# Voltage_Source.net
KiCad netlist of a schematic drawn in Altium Designer
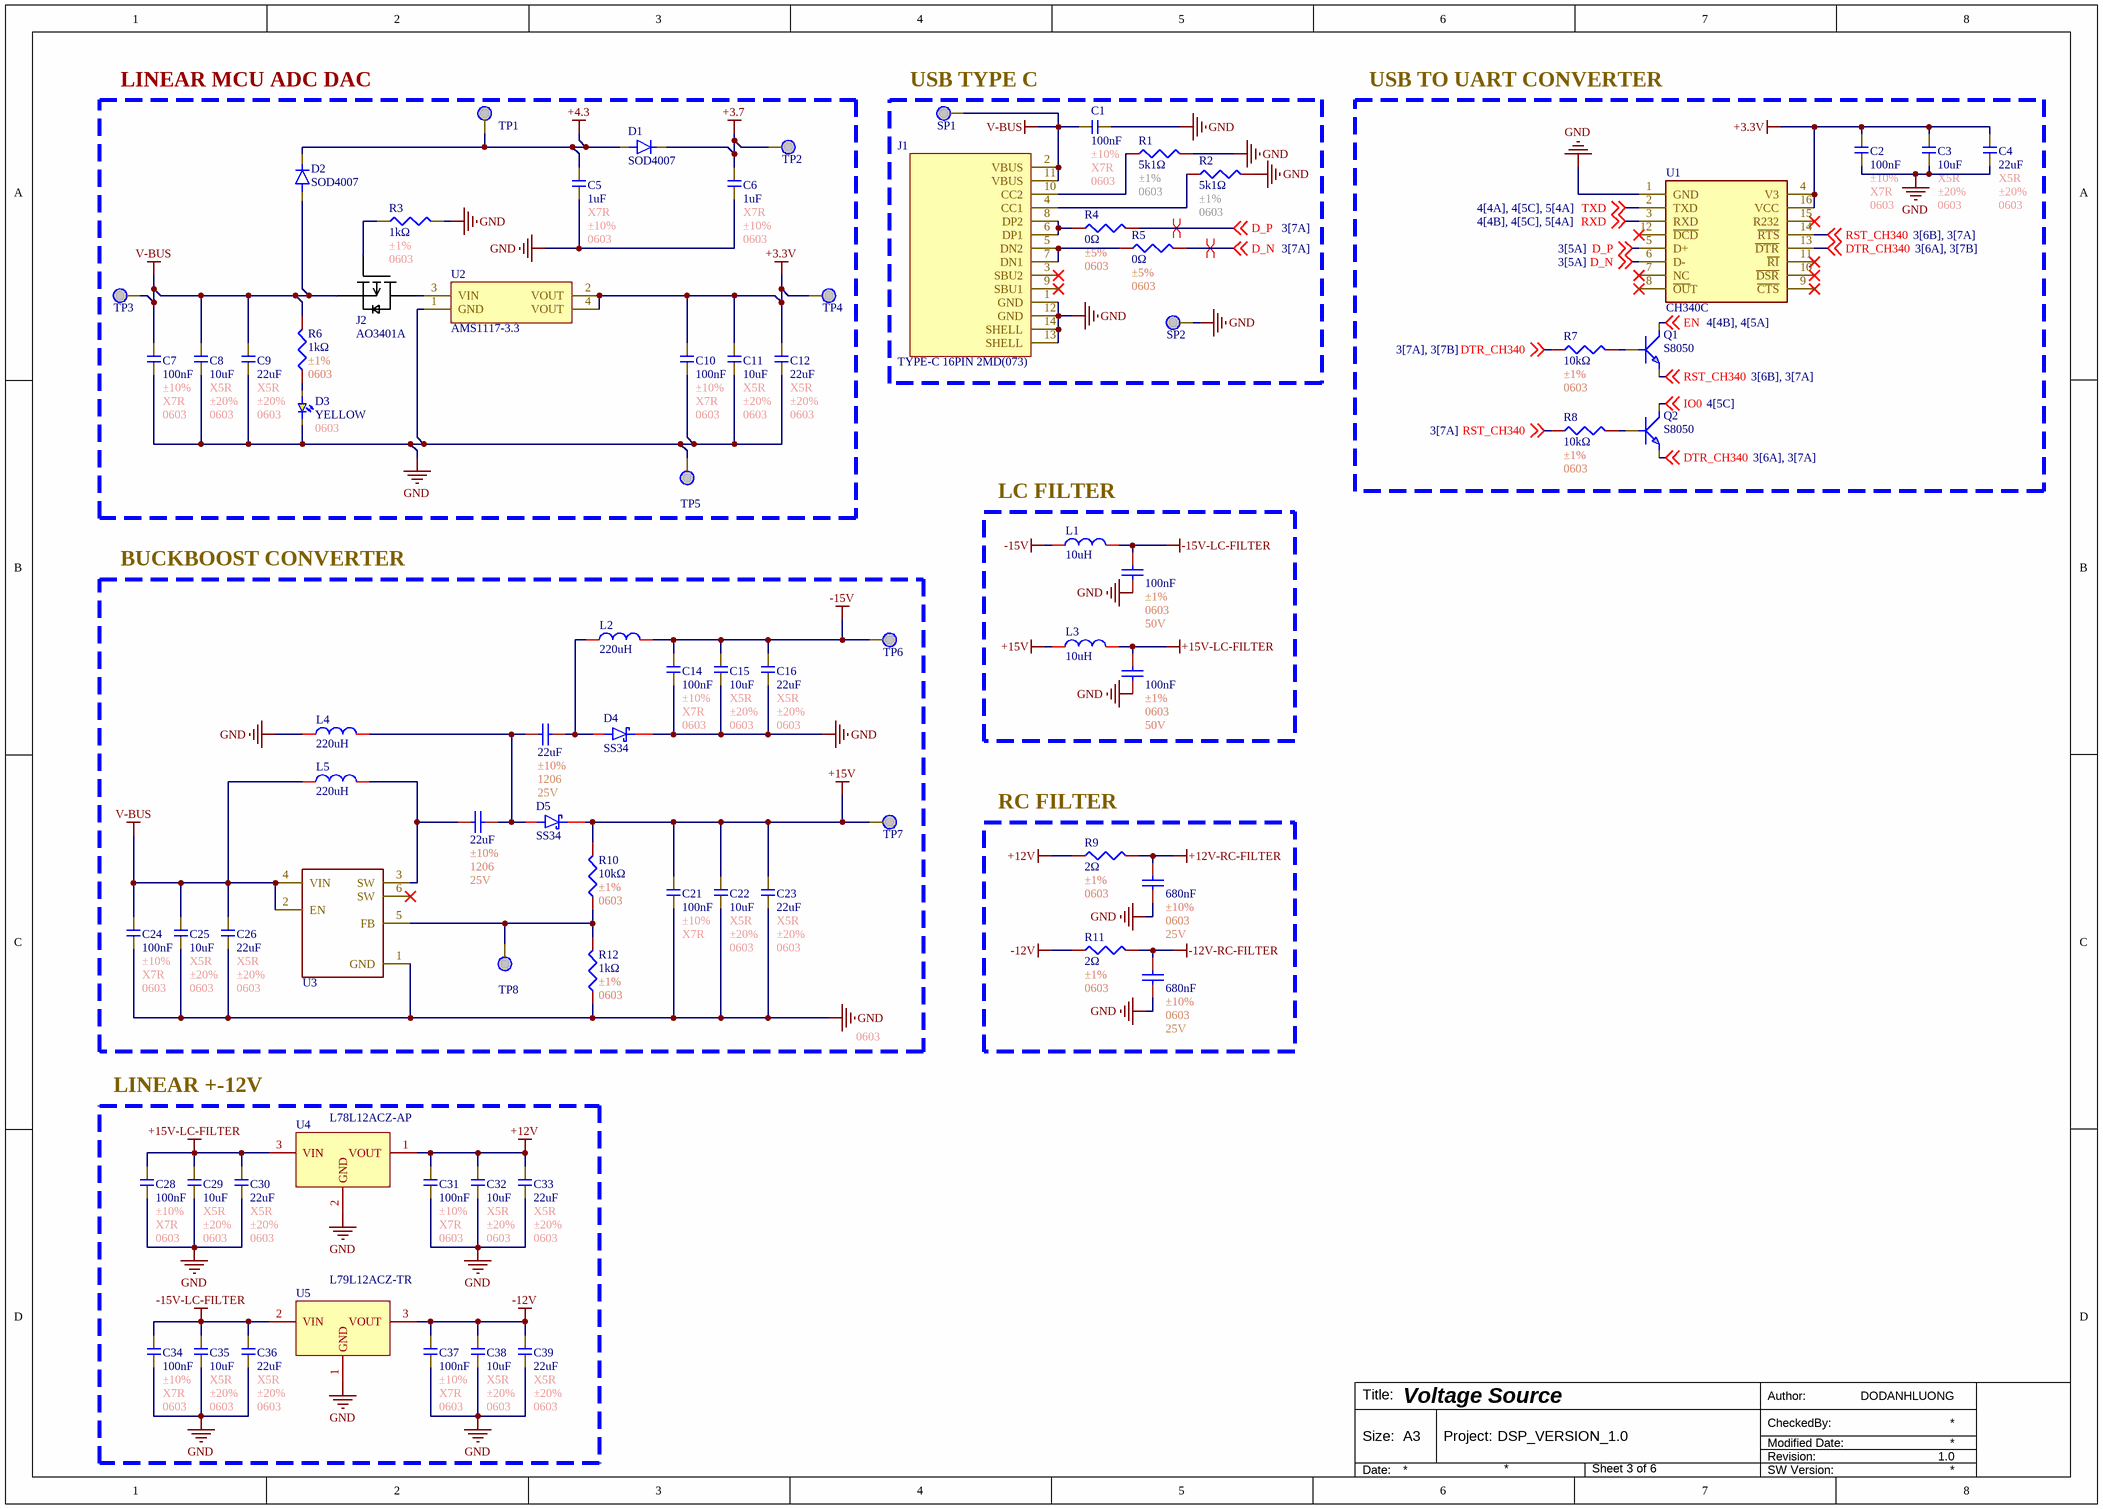
[diagram p0: Voltage Source.SchDoc]

(export (version "E")
  (design (tool "Eeschema 10.0.6"))
  (components
    (comp (ref "C1")
      (value "100nF")
      (footprint "C0603")
      (description "50V 100nF X7R ±10% 0603 Multilayer Ceramic Capacitors MLCC - SMD/SMT ROHS")
      (fields
        (field (name "MANUFACTURER") "YAGEO")
        (field (name "MFR. PART #") "CC0603KRX7R9BB104")
        (field (name "TOLERANCE") "±10%")
        (field (name "TEMPERATURE COEFFICIENT") "X7R")
        (field (name "PACKAGE") "0603")
      )
      (libsource (lib "DSP_VERSION_1.0") (part "C0603_100nF_±10%_X7R"))
    )
    (comp (ref "C2")
      (value "100nF")
      (footprint "C0603")
      (description "50V 100nF X7R ±10% 0603 Multilayer Ceramic Capacitors MLCC - SMD/SMT ROHS")
      (fields
        (field (name "MANUFACTURER") "YAGEO")
        (field (name "MFR. PART #") "CC0603KRX7R9BB104")
        (field (name "TOLERANCE") "±10%")
        (field (name "TEMPERATURE COEFFICIENT") "X7R")
        (field (name "PACKAGE") "0603")
      )
      (libsource (lib "DSP_VERSION_1.0") (part "C0603_100nF_±10%_X7R"))
    )
    (comp (ref "C3")
      (value "10uF")
      (footprint "C0603")
      (description "25V 10uF X5R ±20% 0603 Multilayer Ceramic Capacitors MLCC - SMD/SMT ROHS")
      (fields
        (field (name "MANUFACTURER") "YAGEO")
        (field (name "MFR. PART #") "CC0603MRX5R8BB106")
        (field (name "TEMPERATURE COEFFICIENT") "X5R")
        (field (name "TOLERANCE") "±20%")
        (field (name "PACKAGE") "0603")
      )
      (libsource (lib "DSP_VERSION_1.0") (part "C0603_10uF_±10%_X7R"))
    )
    (comp (ref "C4")
      (value "22uF")
      (footprint "C0603")
      (description "6.3V 22uF X5R ±20% 0603 Multilayer Ceramic Capacitors MLCC - SMD/SMT ROHS")
      (fields
        (field (name "MANUFACTURER") "YAGEO")
        (field (name "MFR. PART #") "CC0603MRX5R5BB226")
        (field (name "TEMPERATURE COEFFICIENT") "X5R")
        (field (name "TOLERANCE") "±20%")
        (field (name "PACKAGE") "0603")
      )
      (libsource (lib "DSP_VERSION_1.0") (part "C0603_22uF_±20%_X5R"))
    )
    (comp (ref "C5")
      (value "1uF")
      (footprint "C0603")
      (description "50V 1uF X7R ±10% 0603 Multilayer Ceramic Capacitors MLCC - SMD/SMT ROHS")
      (fields
        (field (name "MANUFACTURER") "YAGEO")
        (field (name "MFR. PART #") "CC0603KRX7R9BB105")
        (field (name "TEMPERATURE COEFFICIENT") "X7R")
        (field (name "TOLERANCE") "±10%")
        (field (name "PACKAGE") "0603")
      )
      (libsource (lib "DSP_VERSION_1.0") (part "C0603_1uF_±10%_X7R"))
    )
    (comp (ref "C6")
      (value "1uF")
      (footprint "C0603")
      (description "50V 1uF X7R ±10% 0603 Multilayer Ceramic Capacitors MLCC - SMD/SMT ROHS")
      (fields
        (field (name "MANUFACTURER") "YAGEO")
        (field (name "MFR. PART #") "CC0603KRX7R9BB105")
        (field (name "TEMPERATURE COEFFICIENT") "X7R")
        (field (name "TOLERANCE") "±10%")
        (field (name "PACKAGE") "0603")
      )
      (libsource (lib "DSP_VERSION_1.0") (part "C0603_1uF_±10%_X7R"))
    )
    (comp (ref "C7")
      (value "100nF")
      (footprint "C0603")
      (description "50V 100nF X7R ±10% 0603 Multilayer Ceramic Capacitors MLCC - SMD/SMT ROHS")
      (fields
        (field (name "MANUFACTURER") "YAGEO")
        (field (name "MFR. PART #") "CC0603KRX7R9BB104")
        (field (name "TOLERANCE") "±10%")
        (field (name "TEMPERATURE COEFFICIENT") "X7R")
        (field (name "PACKAGE") "0603")
      )
      (libsource (lib "DSP_VERSION_1.0") (part "C0603_100nF_±10%_X7R"))
    )
    (comp (ref "C8")
      (value "10uF")
      (footprint "C0603")
      (description "25V 10uF X5R ±20% 0603 Multilayer Ceramic Capacitors MLCC - SMD/SMT ROHS")
      (fields
        (field (name "MANUFACTURER") "YAGEO")
        (field (name "MFR. PART #") "CC0603MRX5R8BB106")
        (field (name "TEMPERATURE COEFFICIENT") "X5R")
        (field (name "TOLERANCE") "±20%")
        (field (name "PACKAGE") "0603")
      )
      (libsource (lib "DSP_VERSION_1.0") (part "C0603_10uF_±10%_X7R"))
    )
    (comp (ref "C9")
      (value "22uF")
      (footprint "C0603")
      (description "6.3V 22uF X5R ±20% 0603 Multilayer Ceramic Capacitors MLCC - SMD/SMT ROHS")
      (fields
        (field (name "MANUFACTURER") "YAGEO")
        (field (name "MFR. PART #") "CC0603MRX5R5BB226")
        (field (name "TEMPERATURE COEFFICIENT") "X5R")
        (field (name "TOLERANCE") "±20%")
        (field (name "PACKAGE") "0603")
      )
      (libsource (lib "DSP_VERSION_1.0") (part "C0603_22uF_±20%_X5R"))
    )
    (comp (ref "C10")
      (value "100nF")
      (footprint "C0603")
      (description "50V 100nF X7R ±10% 0603 Multilayer Ceramic Capacitors MLCC - SMD/SMT ROHS")
      (fields
        (field (name "MANUFACTURER") "YAGEO")
        (field (name "MFR. PART #") "CC0603KRX7R9BB104")
        (field (name "TOLERANCE") "±10%")
        (field (name "TEMPERATURE COEFFICIENT") "X7R")
        (field (name "PACKAGE") "0603")
      )
      (libsource (lib "DSP_VERSION_1.0") (part "C0603_100nF_±10%_X7R"))
    )
    (comp (ref "C11")
      (value "10uF")
      (footprint "C0603")
      (description "25V 10uF X5R ±20% 0603 Multilayer Ceramic Capacitors MLCC - SMD/SMT ROHS")
      (fields
        (field (name "MANUFACTURER") "YAGEO")
        (field (name "MFR. PART #") "CC0603MRX5R8BB106")
        (field (name "TEMPERATURE COEFFICIENT") "X5R")
        (field (name "TOLERANCE") "±20%")
        (field (name "PACKAGE") "0603")
      )
      (libsource (lib "DSP_VERSION_1.0") (part "C0603_10uF_±10%_X7R"))
    )
    (comp (ref "C12")
      (value "22uF")
      (footprint "C0603")
      (description "6.3V 22uF X5R ±20% 0603 Multilayer Ceramic Capacitors MLCC - SMD/SMT ROHS")
      (fields
        (field (name "MANUFACTURER") "YAGEO")
        (field (name "MFR. PART #") "CC0603MRX5R5BB226")
        (field (name "TEMPERATURE COEFFICIENT") "X5R")
        (field (name "TOLERANCE") "±20%")
        (field (name "PACKAGE") "0603")
      )
      (libsource (lib "DSP_VERSION_1.0") (part "C0603_22uF_±20%_X5R"))
    )
    (comp (ref "C13")
      (value "100nF")
      (footprint "C0603")
      (description "50V 10pF NP0 ±1% 0402 Multilayer Ceramic Capacitors MLCC - SMD/SMT ROHS")
      (fields
        (field (name "MANUFACTURER") "YAGEO")
        (field (name "MFR. PART #") "CC0402FRNPO9BN100")
        (field (name "TOLERANCE") "±1%")
        (field (name "PACKAGE") "0603")
        (field (name "VOLTAGE RATING") "50V")
      )
      (libsource (lib "Capital") (part "C0603_100nF_±1%"))
    )
    (comp (ref "C14")
      (value "100nF")
      (footprint "C0603")
      (description "50V 100nF X7R ±10% 0603 Multilayer Ceramic Capacitors MLCC - SMD/SMT ROHS")
      (fields
        (field (name "MANUFACTURER") "YAGEO")
        (field (name "MFR. PART #") "CC0603KRX7R9BB104")
        (field (name "TOLERANCE") "±10%")
        (field (name "TEMPERATURE COEFFICIENT") "X7R")
        (field (name "PACKAGE") "0603")
      )
      (libsource (lib "DSP_VERSION_1.0") (part "C0603_100nF_±10%_X7R"))
    )
    (comp (ref "C15")
      (value "10uF")
      (footprint "C0603")
      (description "25V 10uF X5R ±20% 0603 Multilayer Ceramic Capacitors MLCC - SMD/SMT ROHS")
      (fields
        (field (name "MANUFACTURER") "YAGEO")
        (field (name "MFR. PART #") "CC0603MRX5R8BB106")
        (field (name "TEMPERATURE COEFFICIENT") "X5R")
        (field (name "TOLERANCE") "±20%")
        (field (name "PACKAGE") "0603")
      )
      (libsource (lib "DSP_VERSION_1.0") (part "C0603_10uF_±10%_X7R"))
    )
    (comp (ref "C16")
      (value "22uF")
      (footprint "C0603")
      (description "6.3V 22uF X5R ±20% 0603 Multilayer Ceramic Capacitors MLCC - SMD/SMT ROHS")
      (fields
        (field (name "MANUFACTURER") "YAGEO")
        (field (name "MFR. PART #") "CC0603MRX5R5BB226")
        (field (name "TEMPERATURE COEFFICIENT") "X5R")
        (field (name "TOLERANCE") "±20%")
        (field (name "PACKAGE") "0603")
      )
      (libsource (lib "DSP_VERSION_1.0") (part "C0603_22uF_±20%_X5R"))
    )
    (comp (ref "C17")
      (value "100nF")
      (footprint "C0603")
      (description "50V 10pF NP0 ±1% 0402 Multilayer Ceramic Capacitors MLCC - SMD/SMT ROHS")
      (fields
        (field (name "MANUFACTURER") "YAGEO")
        (field (name "MFR. PART #") "CC0402FRNPO9BN100")
        (field (name "TOLERANCE") "±1%")
        (field (name "PACKAGE") "0603")
        (field (name "VOLTAGE RATING") "50V")
      )
      (libsource (lib "Capital") (part "C0603_100nF_±1%"))
    )
    (comp (ref "C18")
      (value "22uF")
      (footprint "C1206")
      (description "25V 22uF X5R ±10% 1206 Multilayer Ceramic Capacitors MLCC - SMD/SMT ROHS")
      (fields
        (field (name "MANUFACTURER") "YAGEO")
        (field (name "MFR. PART #") "CC1206KKX5R8BB226")
        (field (name "TOLERANCE") "±10%")
        (field (name "PACKAGE") "1206")
        (field (name "VOLTAGE RATING") "25V")
      )
      (libsource (lib "Capital") (part "C1206_22uF_±1%"))
    )
    (comp (ref "C19")
      (value "22uF")
      (footprint "C1206")
      (description "25V 22uF X5R ±10% 1206 Multilayer Ceramic Capacitors MLCC - SMD/SMT ROHS")
      (fields
        (field (name "MANUFACTURER") "YAGEO")
        (field (name "MFR. PART #") "CC1206KKX5R8BB226")
        (field (name "TOLERANCE") "±10%")
        (field (name "PACKAGE") "1206")
        (field (name "VOLTAGE RATING") "25V")
      )
      (libsource (lib "Capital") (part "C1206_22uF_±1%"))
    )
    (comp (ref "C20")
      (value "680nF")
      (footprint "C0603")
      (description "25V 680nF X5R ±10% 0603 Multilayer Ceramic Capacitors MLCC - SMD/SMT ROHS")
      (fields
        (field (name "MANUFACTURER") "YAGEO")
        (field (name "MFR. PART #") "CC0603KRX5R8BB684")
        (field (name "TOLERANCE") "±10%")
        (field (name "PACKAGE") "0603")
        (field (name "VOLTAGE RATING") "25V")
      )
      (libsource (lib "Capital") (part "C0603_680nF_±1%"))
    )
    (comp (ref "C21")
      (value "100nF")
      (footprint "C0603")
      (description "50V 100nF X7R ±10% 0603 Multilayer Ceramic Capacitors MLCC - SMD/SMT ROHS")
      (fields
        (field (name "MANUFACTURER") "YAGEO")
        (field (name "MFR. PART #") "CC0603KRX7R9BB104")
        (field (name "TOLERANCE") "±10%")
        (field (name "TEMPERATURE COEFFICIENT") "X7R")
        (field (name "PACKAGE") "0603")
      )
      (libsource (lib "DSP_VERSION_1.0") (part "C0603_100nF_±10%_X7R"))
    )
    (comp (ref "C22")
      (value "10uF")
      (footprint "C0603")
      (description "25V 10uF X5R ±20% 0603 Multilayer Ceramic Capacitors MLCC - SMD/SMT ROHS")
      (fields
        (field (name "MANUFACTURER") "YAGEO")
        (field (name "MFR. PART #") "CC0603MRX5R8BB106")
        (field (name "TEMPERATURE COEFFICIENT") "X5R")
        (field (name "TOLERANCE") "±20%")
        (field (name "PACKAGE") "0603")
      )
      (libsource (lib "DSP_VERSION_1.0") (part "C0603_10uF_±10%_X7R"))
    )
    (comp (ref "C23")
      (value "22uF")
      (footprint "C0603")
      (description "6.3V 22uF X5R ±20% 0603 Multilayer Ceramic Capacitors MLCC - SMD/SMT ROHS")
      (fields
        (field (name "MANUFACTURER") "YAGEO")
        (field (name "MFR. PART #") "CC0603MRX5R5BB226")
        (field (name "TEMPERATURE COEFFICIENT") "X5R")
        (field (name "TOLERANCE") "±20%")
        (field (name "PACKAGE") "0603")
      )
      (libsource (lib "DSP_VERSION_1.0") (part "C0603_22uF_±20%_X5R"))
    )
    (comp (ref "C24")
      (value "100nF")
      (footprint "C0603")
      (description "50V 100nF X7R ±10% 0603 Multilayer Ceramic Capacitors MLCC - SMD/SMT ROHS")
      (fields
        (field (name "MANUFACTURER") "YAGEO")
        (field (name "MFR. PART #") "CC0603KRX7R9BB104")
        (field (name "TOLERANCE") "±10%")
        (field (name "TEMPERATURE COEFFICIENT") "X7R")
        (field (name "PACKAGE") "0603")
      )
      (libsource (lib "DSP_VERSION_1.0") (part "C0603_100nF_±10%_X7R"))
    )
    (comp (ref "C25")
      (value "10uF")
      (footprint "C0603")
      (description "25V 10uF X5R ±20% 0603 Multilayer Ceramic Capacitors MLCC - SMD/SMT ROHS")
      (fields
        (field (name "MANUFACTURER") "YAGEO")
        (field (name "MFR. PART #") "CC0603MRX5R8BB106")
        (field (name "TEMPERATURE COEFFICIENT") "X5R")
        (field (name "TOLERANCE") "±20%")
        (field (name "PACKAGE") "0603")
      )
      (libsource (lib "DSP_VERSION_1.0") (part "C0603_10uF_±10%_X7R"))
    )
    (comp (ref "C26")
      (value "22uF")
      (footprint "C0603")
      (description "6.3V 22uF X5R ±20% 0603 Multilayer Ceramic Capacitors MLCC - SMD/SMT ROHS")
      (fields
        (field (name "MANUFACTURER") "YAGEO")
        (field (name "MFR. PART #") "CC0603MRX5R5BB226")
        (field (name "TEMPERATURE COEFFICIENT") "X5R")
        (field (name "TOLERANCE") "±20%")
        (field (name "PACKAGE") "0603")
      )
      (libsource (lib "DSP_VERSION_1.0") (part "C0603_22uF_±20%_X5R"))
    )
    (comp (ref "C27")
      (value "680nF")
      (footprint "C0603")
      (description "25V 680nF X5R ±10% 0603 Multilayer Ceramic Capacitors MLCC - SMD/SMT ROHS")
      (fields
        (field (name "MANUFACTURER") "YAGEO")
        (field (name "MFR. PART #") "CC0603KRX5R8BB684")
        (field (name "TOLERANCE") "±10%")
        (field (name "PACKAGE") "0603")
        (field (name "VOLTAGE RATING") "25V")
      )
      (libsource (lib "Capital") (part "C0603_680nF_±1%"))
    )
    (comp (ref "C28")
      (value "100nF")
      (footprint "C0603")
      (description "50V 100nF X7R ±10% 0603 Multilayer Ceramic Capacitors MLCC - SMD/SMT ROHS")
      (fields
        (field (name "MANUFACTURER") "YAGEO")
        (field (name "MFR. PART #") "CC0603KRX7R9BB104")
        (field (name "TOLERANCE") "±10%")
        (field (name "TEMPERATURE COEFFICIENT") "X7R")
        (field (name "PACKAGE") "0603")
      )
      (libsource (lib "DSP_VERSION_1.0") (part "C0603_100nF_±10%_X7R"))
    )
    (comp (ref "C29")
      (value "10uF")
      (footprint "C0603")
      (description "25V 10uF X5R ±20% 0603 Multilayer Ceramic Capacitors MLCC - SMD/SMT ROHS")
      (fields
        (field (name "MANUFACTURER") "YAGEO")
        (field (name "MFR. PART #") "CC0603MRX5R8BB106")
        (field (name "TEMPERATURE COEFFICIENT") "X5R")
        (field (name "TOLERANCE") "±20%")
        (field (name "PACKAGE") "0603")
      )
      (libsource (lib "DSP_VERSION_1.0") (part "C0603_10uF_±10%_X7R"))
    )
    (comp (ref "C30")
      (value "22uF")
      (footprint "C0603")
      (description "6.3V 22uF X5R ±20% 0603 Multilayer Ceramic Capacitors MLCC - SMD/SMT ROHS")
      (fields
        (field (name "MANUFACTURER") "YAGEO")
        (field (name "MFR. PART #") "CC0603MRX5R5BB226")
        (field (name "TEMPERATURE COEFFICIENT") "X5R")
        (field (name "TOLERANCE") "±20%")
        (field (name "PACKAGE") "0603")
      )
      (libsource (lib "DSP_VERSION_1.0") (part "C0603_22uF_±20%_X5R"))
    )
    (comp (ref "C31")
      (value "100nF")
      (footprint "C0603")
      (description "50V 100nF X7R ±10% 0603 Multilayer Ceramic Capacitors MLCC - SMD/SMT ROHS")
      (fields
        (field (name "MANUFACTURER") "YAGEO")
        (field (name "MFR. PART #") "CC0603KRX7R9BB104")
        (field (name "TOLERANCE") "±10%")
        (field (name "TEMPERATURE COEFFICIENT") "X7R")
        (field (name "PACKAGE") "0603")
      )
      (libsource (lib "DSP_VERSION_1.0") (part "C0603_100nF_±10%_X7R"))
    )
    (comp (ref "C32")
      (value "10uF")
      (footprint "C0603")
      (description "25V 10uF X5R ±20% 0603 Multilayer Ceramic Capacitors MLCC - SMD/SMT ROHS")
      (fields
        (field (name "MANUFACTURER") "YAGEO")
        (field (name "MFR. PART #") "CC0603MRX5R8BB106")
        (field (name "TEMPERATURE COEFFICIENT") "X5R")
        (field (name "TOLERANCE") "±20%")
        (field (name "PACKAGE") "0603")
      )
      (libsource (lib "DSP_VERSION_1.0") (part "C0603_10uF_±10%_X7R"))
    )
    (comp (ref "C33")
      (value "22uF")
      (footprint "C0603")
      (description "6.3V 22uF X5R ±20% 0603 Multilayer Ceramic Capacitors MLCC - SMD/SMT ROHS")
      (fields
        (field (name "MANUFACTURER") "YAGEO")
        (field (name "MFR. PART #") "CC0603MRX5R5BB226")
        (field (name "TEMPERATURE COEFFICIENT") "X5R")
        (field (name "TOLERANCE") "±20%")
        (field (name "PACKAGE") "0603")
      )
      (libsource (lib "DSP_VERSION_1.0") (part "C0603_22uF_±20%_X5R"))
    )
    (comp (ref "C34")
      (value "100nF")
      (footprint "C0603")
      (description "50V 100nF X7R ±10% 0603 Multilayer Ceramic Capacitors MLCC - SMD/SMT ROHS")
      (fields
        (field (name "MANUFACTURER") "YAGEO")
        (field (name "MFR. PART #") "CC0603KRX7R9BB104")
        (field (name "TOLERANCE") "±10%")
        (field (name "TEMPERATURE COEFFICIENT") "X7R")
        (field (name "PACKAGE") "0603")
      )
      (libsource (lib "DSP_VERSION_1.0") (part "C0603_100nF_±10%_X7R"))
    )
    (comp (ref "C35")
      (value "10uF")
      (footprint "C0603")
      (description "25V 10uF X5R ±20% 0603 Multilayer Ceramic Capacitors MLCC - SMD/SMT ROHS")
      (fields
        (field (name "MANUFACTURER") "YAGEO")
        (field (name "MFR. PART #") "CC0603MRX5R8BB106")
        (field (name "TEMPERATURE COEFFICIENT") "X5R")
        (field (name "TOLERANCE") "±20%")
        (field (name "PACKAGE") "0603")
      )
      (libsource (lib "DSP_VERSION_1.0") (part "C0603_10uF_±10%_X7R"))
    )
    (comp (ref "C36")
      (value "22uF")
      (footprint "C0603")
      (description "6.3V 22uF X5R ±20% 0603 Multilayer Ceramic Capacitors MLCC - SMD/SMT ROHS")
      (fields
        (field (name "MANUFACTURER") "YAGEO")
        (field (name "MFR. PART #") "CC0603MRX5R5BB226")
        (field (name "TEMPERATURE COEFFICIENT") "X5R")
        (field (name "TOLERANCE") "±20%")
        (field (name "PACKAGE") "0603")
      )
      (libsource (lib "DSP_VERSION_1.0") (part "C0603_22uF_±20%_X5R"))
    )
    (comp (ref "C37")
      (value "100nF")
      (footprint "C0603")
      (description "50V 100nF X7R ±10% 0603 Multilayer Ceramic Capacitors MLCC - SMD/SMT ROHS")
      (fields
        (field (name "MANUFACTURER") "YAGEO")
        (field (name "MFR. PART #") "CC0603KRX7R9BB104")
        (field (name "TOLERANCE") "±10%")
        (field (name "TEMPERATURE COEFFICIENT") "X7R")
        (field (name "PACKAGE") "0603")
      )
      (libsource (lib "DSP_VERSION_1.0") (part "C0603_100nF_±10%_X7R"))
    )
    (comp (ref "C38")
      (value "10uF")
      (footprint "C0603")
      (description "25V 10uF X5R ±20% 0603 Multilayer Ceramic Capacitors MLCC - SMD/SMT ROHS")
      (fields
        (field (name "MANUFACTURER") "YAGEO")
        (field (name "MFR. PART #") "CC0603MRX5R8BB106")
        (field (name "TEMPERATURE COEFFICIENT") "X5R")
        (field (name "TOLERANCE") "±20%")
        (field (name "PACKAGE") "0603")
      )
      (libsource (lib "DSP_VERSION_1.0") (part "C0603_10uF_±10%_X7R"))
    )
    (comp (ref "C39")
      (value "22uF")
      (footprint "C0603")
      (description "6.3V 22uF X5R ±20% 0603 Multilayer Ceramic Capacitors MLCC - SMD/SMT ROHS")
      (fields
        (field (name "MANUFACTURER") "YAGEO")
        (field (name "MFR. PART #") "CC0603MRX5R5BB226")
        (field (name "TEMPERATURE COEFFICIENT") "X5R")
        (field (name "TOLERANCE") "±20%")
        (field (name "PACKAGE") "0603")
      )
      (libsource (lib "DSP_VERSION_1.0") (part "C0603_22uF_±20%_X5R"))
    )
    (comp (ref "D1")
      (value "SOD4007")
      (footprint "SOD4007")
      (description "1A Independent 1kV 1.1V@1A SOD-123FL Diodes - General Purpose ROHS")
      (fields
        (field (name "MANUFACTURER") "MDD(Microdiode Semiconductor)")
        (field (name "LCSC PART #") "C18124")
      )
      (libsource (lib "Diode") (part "SOD4007"))
    )
    (comp (ref "D2")
      (value "SOD4007")
      (footprint "SOD4007")
      (description "1A Independent 1kV 1.1V@1A SOD-123FL Diodes - General Purpose ROHS")
      (fields
        (field (name "MANUFACTURER") "MDD(Microdiode Semiconductor)")
        (field (name "LCSC PART #") "C18124")
      )
      (libsource (lib "Diode") (part "SOD4007"))
    )
    (comp (ref "D3")
      (value "YELLOW")
      (footprint "LED0603")
      (description "25mcd~40mcd Water Clear -40℃~+85℃ 624nm Red 120° 60mW 0402 LED Indication - Discrete ROHS")
      (fields
        (field (name "MANUFACTURER") "XINGLIGHT")
        (field (name "MFR. PART #") "XL-1005UGC")
        (field (name "PACKAGE") "0603")
      )
      (libsource (lib "LED") (part "D0603_YELLOW"))
    )
    (comp (ref "D4")
      (value "SS34")
      (footprint "SS34")
      (description "40V Independent 3A 550mV@3A SMA(DO-214AC) Schottky Diodes ROHS")
      (fields
        (field (name "MANUFACTURER") "MDD(Microdiode Semiconductor)")
        (field (name "LCSC PART #") "C8678")
      )
      (libsource (lib "Diode") (part "SS34"))
    )
    (comp (ref "D5")
      (value "SS34")
      (footprint "SS34")
      (description "40V Independent 3A 550mV@3A SMA(DO-214AC) Schottky Diodes ROHS")
      (fields
        (field (name "MANUFACTURER") "MDD(Microdiode Semiconductor)")
        (field (name "LCSC PART #") "C8678")
      )
      (libsource (lib "Diode") (part "SS34"))
    )
    (comp (ref "J1")
      (value "TYPE-C 16PIN 2MD(073)")
      (footprint "TYPE_C_FAMALE")
      (description "3A 1 Surface Mount, Right Angle 16P Female -25℃~+85℃ Type-C SMD USB Connectors ROHS")
      (fields (field (name "MANUFACTURER") "SHOU HAN") (field (name "LCSC PART #") "C2765186"))
      (libsource (lib "Connector") (part "TYPE_C_FAMALE_16PIN"))
    )
    (comp (ref "J2")
      (value "AO3401A")
      (footprint "AO3401A")
      (description "30V 4A 900mV@250uA 1 P-Channel SOT-23 MOSFETs ROHS")
      (fields (field (name "MANUFACTURER") "AOS") (field (name "LCSC PART #") "C15127"))
      (libsource (lib "DSP_VERSION_1.0") (part "AO3401"))
    )
    (comp (ref "L1")
      (value "10uH")
      (footprint "CD43")
      (description "1.15A 10uH Unshielded Inductor ±20% SMD,4x4.5mm Power Inductors ROHS")
      (fields (field (name "MANUFACTURER") "ZE") (field (name "MFR. PART #") "CD43-100M"))
      (libsource (lib "Inductor") (part "CD4-10UH"))
    )
    (comp (ref "L2")
      (value "220uH")
      (footprint "CD43")
      (description "360mA 220uH ±20% SMD,4.5x4x3.2mm Power Inductors ROHS")
      (fields (field (name "MANUFACTURER") "YJYCOIN") (field (name "MFR. PART #") "CD43YP0403-221M"))
      (libsource (lib "Inductor") (part "CD4-220UH"))
    )
    (comp (ref "L3")
      (value "10uH")
      (footprint "CD43")
      (description "1.15A 10uH Unshielded Inductor ±20% SMD,4x4.5mm Power Inductors ROHS")
      (fields (field (name "MANUFACTURER") "ZE") (field (name "MFR. PART #") "CD43-100M"))
      (libsource (lib "Inductor") (part "CD4-10UH"))
    )
    (comp (ref "L4")
      (value "220uH")
      (footprint "CD43")
      (description "360mA 220uH ±20% SMD,4.5x4x3.2mm Power Inductors ROHS")
      (fields (field (name "MANUFACTURER") "YJYCOIN") (field (name "MFR. PART #") "CD43YP0403-221M"))
      (libsource (lib "Inductor") (part "CD4-220UH"))
    )
    (comp (ref "L5")
      (value "220uH")
      (footprint "CD43")
      (description "360mA 220uH ±20% SMD,4.5x4x3.2mm Power Inductors ROHS")
      (fields (field (name "MANUFACTURER") "YJYCOIN") (field (name "MFR. PART #") "CD43YP0403-221M"))
      (libsource (lib "Inductor") (part "CD4-220UH"))
    )
    (comp (ref "Q1")
      (value "S8050")
      (footprint "S8050")
      (description "25V 300mW 500mA SOT-23 Bipolar (BJT) ROHS")
      (fields (field (name "MANUFACTURER") "JSMSEMI") (field (name "LCSC PART #") "C916390"))
      (libsource (lib "Transistor") (part "S8050"))
    )
    (comp (ref "Q2")
      (value "S8050")
      (footprint "S8050")
      (description "25V 300mW 500mA SOT-23 Bipolar (BJT) ROHS")
      (fields (field (name "MANUFACTURER") "JSMSEMI") (field (name "LCSC PART #") "C916390"))
      (libsource (lib "Transistor") (part "S8050"))
    )
    (comp (ref "R1")
      (value "5k1Ω")
      (footprint "R0603")
      (description "100mW Thick Film Resistor 75V ±100ppm/℃ ±1% 5.1kΩ 0603 Chip Resistor - Surface Mount ROHS")
      (fields
        (field (name "MANUFACTURER") "FOJAN")
        (field (name "MFR. PART #") "FRC0603F5101TS")
        (field (name "TOLERANCE") "±1%")
        (field (name "PACKAGE") "0603")
      )
      (libsource (lib "Resistor") (part "R0603_5k1Ω_±1%"))
    )
    (comp (ref "R2")
      (value "5k1Ω")
      (footprint "R0603")
      (description "100mW Thick Film Resistor 75V ±100ppm/℃ ±1% 5.1kΩ 0603 Chip Resistor - Surface Mount ROHS")
      (fields
        (field (name "MANUFACTURER") "FOJAN")
        (field (name "MFR. PART #") "FRC0603F5101TS")
        (field (name "TOLERANCE") "±1%")
        (field (name "PACKAGE") "0603")
      )
      (libsource (lib "Resistor") (part "R0603_5k1Ω_±1%"))
    )
    (comp (ref "R3")
      (value "1kΩ")
      (footprint "R0603")
      (description "100mW Thick Film Resistor 75V ±100ppm/℃ ±1% 1kΩ 0603 Chip Resistor - Surface Mount ROHS")
      (fields
        (field (name "MANUFACTURER") "YAGEO")
        (field (name "MFR. PART #") "RC0603FR-071KL")
        (field (name "TOLERANCE") "±1%")
        (field (name "PACKAGE") "0603")
      )
      (libsource (lib "DSP_VERSION_1.0") (part "R0603_1kΩ_±1%"))
    )
    (comp (ref "R4")
      (value "0Ω")
      (footprint "R0603")
      (description "100mW Thick Film Resistor 75V ±5% 0Ω 0603 Chip Resistor - Surface Mount ROHS")
      (fields
        (field (name "MANUFACTURER") "YAGEO")
        (field (name "MFR. PART #") "RC0603JR-070RL")
        (field (name "TOLERANCE") "±5%")
        (field (name "PACKAGE") "0603")
      )
      (libsource (lib "Resistor") (part "R0603_0Ω_±5%"))
    )
    (comp (ref "R5")
      (value "0Ω")
      (footprint "R0603")
      (description "100mW Thick Film Resistor 75V ±5% 0Ω 0603 Chip Resistor - Surface Mount ROHS")
      (fields
        (field (name "MANUFACTURER") "YAGEO")
        (field (name "MFR. PART #") "RC0603JR-070RL")
        (field (name "TOLERANCE") "±5%")
        (field (name "PACKAGE") "0603")
      )
      (libsource (lib "Resistor") (part "R0603_0Ω_±5%"))
    )
    (comp (ref "R6")
      (value "1kΩ")
      (footprint "R0603")
      (description "62.5mW Thick Film Resistor 50V ±1% ±200ppm/℃ 10Ω 0402 Chip Resistor - Surface Mount ROHS")
      (fields
        (field (name "MANUFACTURER") "YAGEO")
        (field (name "MFR. PART #") "RC0402FR-0710RL")
        (field (name "TOLERANCE") "±1%")
        (field (name "PACKAGE") "0603")
      )
      (libsource (lib "Resistor") (part "R0603_1kΩ_±1%"))
    )
    (comp (ref "R7")
      (value "10kΩ")
      (footprint "R0603")
      (description "62.5mW Thick Film Resistor 50V ±1% ±200ppm/℃ 10Ω 0402 Chip Resistor - Surface Mount ROHS")
      (fields
        (field (name "MANUFACTURER") "YAGEO")
        (field (name "MFR. PART #") "RC0402FR-0710RL")
        (field (name "TOLERANCE") "±1%")
        (field (name "PACKAGE") "0603")
      )
      (libsource (lib "Resistor") (part "R0603_10kΩ_±1%"))
    )
    (comp (ref "R8")
      (value "10kΩ")
      (footprint "R0603")
      (description "62.5mW Thick Film Resistor 50V ±1% ±200ppm/℃ 10Ω 0402 Chip Resistor - Surface Mount ROHS")
      (fields
        (field (name "MANUFACTURER") "YAGEO")
        (field (name "MFR. PART #") "RC0402FR-0710RL")
        (field (name "TOLERANCE") "±1%")
        (field (name "PACKAGE") "0603")
      )
      (libsource (lib "Resistor") (part "R0603_10kΩ_±1%"))
    )
    (comp (ref "R9")
      (value "2Ω")
      (footprint "R0603")
      (description "100mW Thick Film Resistor 75V ±1% ±200ppm/℃ 2Ω 0603 Chip Resistor - Surface Mount ROHS")
      (fields
        (field (name "MANUFACTURER") "YAGEO")
        (field (name "MFR. PART #") "RC0603FR-072RL")
        (field (name "TOLERANCE") "±1%")
        (field (name "PACKAGE") "0603")
      )
      (libsource (lib "Resistor") (part "R0603_2Ω_±5%"))
    )
    (comp (ref "R10")
      (value "10kΩ")
      (footprint "R0603")
      (description "62.5mW Thick Film Resistor 50V ±1% ±200ppm/℃ 10Ω 0402 Chip Resistor - Surface Mount ROHS")
      (fields
        (field (name "MANUFACTURER") "YAGEO")
        (field (name "MFR. PART #") "RC0402FR-0710RL")
        (field (name "TOLERANCE") "±1%")
        (field (name "PACKAGE") "0603")
      )
      (libsource (lib "Resistor") (part "R0603_10kΩ_±1%"))
    )
    (comp (ref "R11")
      (value "2Ω")
      (footprint "R0603")
      (description "100mW Thick Film Resistor 75V ±1% ±200ppm/℃ 2Ω 0603 Chip Resistor - Surface Mount ROHS")
      (fields
        (field (name "MANUFACTURER") "YAGEO")
        (field (name "MFR. PART #") "RC0603FR-072RL")
        (field (name "TOLERANCE") "±1%")
        (field (name "PACKAGE") "0603")
      )
      (libsource (lib "Resistor") (part "R0603_2Ω_±5%"))
    )
    (comp (ref "R12")
      (value "1kΩ")
      (footprint "R0603")
      (description "62.5mW Thick Film Resistor 50V ±1% ±200ppm/℃ 10Ω 0402 Chip Resistor - Surface Mount ROHS")
      (fields
        (field (name "MANUFACTURER") "YAGEO")
        (field (name "MFR. PART #") "RC0402FR-0710RL")
        (field (name "TOLERANCE") "±1%")
        (field (name "PACKAGE") "0603")
      )
      (libsource (lib "Resistor") (part "R0603_1kΩ_±1%"))
    )
    (comp (ref "SP1") (value "SP") (footprint "SP") (libsource (lib "Other") (part "SP")))
    (comp (ref "SP2") (value "SP") (footprint "SP") (libsource (lib "Other") (part "SP")))
    (comp (ref "TP1") (value "TP") (footprint "TP") (libsource (lib "Other") (part "TP")))
    (comp (ref "TP2") (value "TP") (footprint "TP") (libsource (lib "Other") (part "TP")))
    (comp (ref "TP3") (value "TP") (footprint "TP") (libsource (lib "Other") (part "TP")))
    (comp (ref "TP4") (value "TP") (footprint "TP") (libsource (lib "Other") (part "TP")))
    (comp (ref "TP5") (value "TP") (footprint "TP") (libsource (lib "Other") (part "TP")))
    (comp (ref "TP6") (value "TP") (footprint "TP") (libsource (lib "Other") (part "TP")))
    (comp (ref "TP7") (value "TP") (footprint "TP") (libsource (lib "Other") (part "TP")))
    (comp (ref "TP8") (value "TP") (footprint "TP") (libsource (lib "Other") (part "TP")))
    (comp (ref "U1")
      (value "CH340C")
      (footprint "CH340C")
      (description "2Mbps Transceiver USB 2.0 SOP-16 USB Converters ROHS")
      (fields (field (name "MANUFACTURER") "WCH") (field (name "LCSC PART #") "C84681"))
      (libsource (lib "IC") (part "CH340C"))
    )
    (comp (ref "U2")
      (value "AMS1117-3.3")
      (footprint "AMS1117-3.3")
      (fields
        (field (name "MANUFACTURER") "Advanced Monolithic Systems")
        (field (name "LCSC PART #") "C6186")
      )
      (libsource (lib "IC") (part "AMS1117-3.3"))
    )
    (comp (ref "U3") (value "XL6009") (footprint "XL6009") (libsource (lib "IC") (part "XL6009")))
    (comp (ref "U4")
      (value "L78L12ACZ-AP")
      (footprint "L78L12ACZ-AP")
      (fields (field (name "LCSC PART #") "C262913"))
      (libsource (lib "IC") (part "L7812CV-DG"))
    )
    (comp (ref "U5")
      (value "L79L12ACZ-TR")
      (footprint "L79L12ACZ-TR")
      (fields (field (name "LCSC PART #") "C2942984"))
      (libsource (lib "IC") (part "L79L12ACZ-TR"))
    )
  )
  (nets
    (net (code "1") (name "+3.3V") (class "Default")
      (node (ref "C10") (pin "2") (pinfunction "2_2") (pintype "passive"))
      (node (ref "C11") (pin "2") (pinfunction "2_2") (pintype "passive"))
      (node (ref "C12") (pin "2") (pinfunction "2_2") (pintype "passive"))
      (node (ref "C2") (pin "2") (pinfunction "2_2") (pintype "passive"))
      (node (ref "C3") (pin "2") (pinfunction "2_2") (pintype "passive"))
      (node (ref "C4") (pin "2") (pinfunction "2_2") (pintype "passive"))
      (node (ref "TP4") (pin "1") (pinfunction "1_1") (pintype "passive"))
      (node (ref "U1") (pin "16") (pinfunction "VCC_16") (pintype "passive"))
      (node (ref "U1") (pin "4") (pinfunction "V3_4") (pintype "passive"))
      (node (ref "U2") (pin "2") (pinfunction "VOUT_2") (pintype "passive"))
      (node (ref "U2") (pin "4") (pinfunction "VOUT_4") (pintype "passive"))
    )
    (net (code "2") (name "+3.7") (class "Default")
      (node (ref "C6") (pin "2") (pinfunction "2_2") (pintype "passive"))
      (node (ref "D1") (pin "1") (pinfunction "C_1") (pintype "passive"))
      (node (ref "TP2") (pin "1") (pinfunction "1_1") (pintype "passive"))
    )
    (net (code "3") (name "+4.3") (class "Default")
      (node (ref "C5") (pin "2") (pinfunction "2_2") (pintype "passive"))
      (node (ref "D1") (pin "2") (pinfunction "A_2") (pintype "passive"))
      (node (ref "D2") (pin "1") (pinfunction "C_1") (pintype "passive"))
      (node (ref "TP1") (pin "1") (pinfunction "1_1") (pintype "passive"))
    )
    (net (code "4") (name "+12V") (class "Default")
      (node (ref "C31") (pin "2") (pinfunction "2_2") (pintype "passive"))
      (node (ref "C32") (pin "2") (pinfunction "2_2") (pintype "passive"))
      (node (ref "C33") (pin "2") (pinfunction "2_2") (pintype "passive"))
      (node (ref "R9") (pin "1") (pinfunction "1_1") (pintype "passive"))
      (node (ref "U4") (pin "1") (pinfunction "VOUT_1") (pintype "passive"))
    )
    (net (code "5") (name "+12V-RC-FILTER") (class "Default")
      (node (ref "C20") (pin "1") (pinfunction "1_1") (pintype "passive"))
      (node (ref "R9") (pin "2") (pinfunction "2_2") (pintype "passive"))
    )
    (net (code "6") (name "+15V") (class "Default")
      (node (ref "C21") (pin "2") (pinfunction "2_2") (pintype "passive"))
      (node (ref "C22") (pin "2") (pinfunction "2_2") (pintype "passive"))
      (node (ref "C23") (pin "2") (pinfunction "2_2") (pintype "passive"))
      (node (ref "D5") (pin "1") (pinfunction "1_1") (pintype "passive"))
      (node (ref "L3") (pin "1") (pinfunction "1_1") (pintype "passive"))
      (node (ref "R10") (pin "2") (pinfunction "2_2") (pintype "passive"))
      (node (ref "TP7") (pin "1") (pinfunction "1_1") (pintype "passive"))
    )
    (net (code "7") (name "+15V-LC-FILTER") (class "Default")
      (node (ref "C17") (pin "1") (pinfunction "1_1") (pintype "passive"))
      (node (ref "C28") (pin "2") (pinfunction "2_2") (pintype "passive"))
      (node (ref "C29") (pin "2") (pinfunction "2_2") (pintype "passive"))
      (node (ref "C30") (pin "2") (pinfunction "2_2") (pintype "passive"))
      (node (ref "L3") (pin "2") (pinfunction "2_2") (pintype "passive"))
      (node (ref "U4") (pin "3") (pinfunction "VIN_3") (pintype "passive"))
    )
    (net (code "8") (name "-12V") (class "Default")
      (node (ref "C37") (pin "2") (pinfunction "2_2") (pintype "passive"))
      (node (ref "C38") (pin "2") (pinfunction "2_2") (pintype "passive"))
      (node (ref "C39") (pin "2") (pinfunction "2_2") (pintype "passive"))
      (node (ref "R11") (pin "1") (pinfunction "1_1") (pintype "passive"))
      (node (ref "U5") (pin "3") (pinfunction "VOUT_3") (pintype "passive"))
    )
    (net (code "9") (name "-12V-RC-FILTER") (class "Default")
      (node (ref "C27") (pin "1") (pinfunction "1_1") (pintype "passive"))
      (node (ref "R11") (pin "2") (pinfunction "2_2") (pintype "passive"))
    )
    (net (code "10") (name "-15V") (class "Default")
      (node (ref "C14") (pin "2") (pinfunction "2_2") (pintype "passive"))
      (node (ref "C15") (pin "2") (pinfunction "2_2") (pintype "passive"))
      (node (ref "C16") (pin "2") (pinfunction "2_2") (pintype "passive"))
      (node (ref "L1") (pin "1") (pinfunction "1_1") (pintype "passive"))
      (node (ref "L2") (pin "2") (pinfunction "2_2") (pintype "passive"))
      (node (ref "TP6") (pin "1") (pinfunction "1_1") (pintype "passive"))
    )
    (net (code "11") (name "-15V-LC-FILTER") (class "Default")
      (node (ref "C13") (pin "1") (pinfunction "1_1") (pintype "passive"))
      (node (ref "C34") (pin "2") (pinfunction "2_2") (pintype "passive"))
      (node (ref "C35") (pin "2") (pinfunction "2_2") (pintype "passive"))
      (node (ref "C36") (pin "2") (pinfunction "2_2") (pintype "passive"))
      (node (ref "L1") (pin "2") (pinfunction "2_2") (pintype "passive"))
      (node (ref "U5") (pin "2") (pinfunction "VIN_2") (pintype "passive"))
    )
    (net (code "12") (name "DTR_CH340") (class "Default")
      (node (ref "Q2") (pin "2") (pinfunction "E_2") (pintype "passive"))
      (node (ref "R7") (pin "1") (pinfunction "1_1") (pintype "passive"))
      (node (ref "U1") (pin "13") (pinfunction "~{DTR}_13") (pintype "passive"))
    )
    (net (code "13") (name "D_N") (class "Default")
      (node (ref "R5") (pin "2") (pinfunction "2_2") (pintype "passive"))
      (node (ref "U1") (pin "6") (pinfunction "D-_6") (pintype "passive"))
    )
    (net (code "14") (name "D_P") (class "Default")
      (node (ref "R4") (pin "2") (pinfunction "2_2") (pintype "passive"))
      (node (ref "U1") (pin "5") (pinfunction "D+_5") (pintype "passive"))
    )
    (net (code "15") (name "EN") (class "Default")
      (node (ref "Q1") (pin "3") (pinfunction "C_3") (pintype "passive"))
    )
    (net (code "16") (name "GND") (class "Default")
      (node (ref "C1") (pin "1") (pinfunction "1_1") (pintype "passive"))
      (node (ref "C10") (pin "1") (pinfunction "1_1") (pintype "passive"))
      (node (ref "C11") (pin "1") (pinfunction "1_1") (pintype "passive"))
      (node (ref "C12") (pin "1") (pinfunction "1_1") (pintype "passive"))
      (node (ref "C13") (pin "2") (pinfunction "2_2") (pintype "passive"))
      (node (ref "C14") (pin "1") (pinfunction "1_1") (pintype "passive"))
      (node (ref "C15") (pin "1") (pinfunction "1_1") (pintype "passive"))
      (node (ref "C16") (pin "1") (pinfunction "1_1") (pintype "passive"))
      (node (ref "C17") (pin "2") (pinfunction "2_2") (pintype "passive"))
      (node (ref "C2") (pin "1") (pinfunction "1_1") (pintype "passive"))
      (node (ref "C20") (pin "2") (pinfunction "2_2") (pintype "passive"))
      (node (ref "C21") (pin "1") (pinfunction "1_1") (pintype "passive"))
      (node (ref "C22") (pin "1") (pinfunction "1_1") (pintype "passive"))
      (node (ref "C23") (pin "1") (pinfunction "1_1") (pintype "passive"))
      (node (ref "C24") (pin "1") (pinfunction "1_1") (pintype "passive"))
      (node (ref "C25") (pin "1") (pinfunction "1_1") (pintype "passive"))
      (node (ref "C26") (pin "1") (pinfunction "1_1") (pintype "passive"))
      (node (ref "C27") (pin "2") (pinfunction "2_2") (pintype "passive"))
      (node (ref "C28") (pin "1") (pinfunction "1_1") (pintype "passive"))
      (node (ref "C29") (pin "1") (pinfunction "1_1") (pintype "passive"))
      (node (ref "C3") (pin "1") (pinfunction "1_1") (pintype "passive"))
      (node (ref "C30") (pin "1") (pinfunction "1_1") (pintype "passive"))
      (node (ref "C31") (pin "1") (pinfunction "1_1") (pintype "passive"))
      (node (ref "C32") (pin "1") (pinfunction "1_1") (pintype "passive"))
      (node (ref "C33") (pin "1") (pinfunction "1_1") (pintype "passive"))
      (node (ref "C34") (pin "1") (pinfunction "1_1") (pintype "passive"))
      (node (ref "C35") (pin "1") (pinfunction "1_1") (pintype "passive"))
      (node (ref "C36") (pin "1") (pinfunction "1_1") (pintype "passive"))
      (node (ref "C37") (pin "1") (pinfunction "1_1") (pintype "passive"))
      (node (ref "C38") (pin "1") (pinfunction "1_1") (pintype "passive"))
      (node (ref "C39") (pin "1") (pinfunction "1_1") (pintype "passive"))
      (node (ref "C4") (pin "1") (pinfunction "1_1") (pintype "passive"))
      (node (ref "C5") (pin "1") (pinfunction "1_1") (pintype "passive"))
      (node (ref "C6") (pin "1") (pinfunction "1_1") (pintype "passive"))
      (node (ref "C7") (pin "1") (pinfunction "1_1") (pintype "passive"))
      (node (ref "C8") (pin "1") (pinfunction "1_1") (pintype "passive"))
      (node (ref "C9") (pin "1") (pinfunction "1_1") (pintype "passive"))
      (node (ref "D3") (pin "1") (pinfunction "1_1") (pintype "passive"))
      (node (ref "D4") (pin "1") (pinfunction "1_1") (pintype "passive"))
      (node (ref "J1") (pin "1") (pinfunction "GND_1") (pintype "passive"))
      (node (ref "J1") (pin "12") (pinfunction "GND_12") (pintype "passive"))
      (node (ref "J1") (pin "13") (pinfunction "SHELL_13") (pintype "passive"))
      (node (ref "J1") (pin "14") (pinfunction "SHELL_14") (pintype "passive"))
      (node (ref "L4") (pin "1") (pinfunction "1_1") (pintype "passive"))
      (node (ref "R1") (pin "2") (pinfunction "2_2") (pintype "passive"))
      (node (ref "R12") (pin "1") (pinfunction "1_1") (pintype "passive"))
      (node (ref "R2") (pin "2") (pinfunction "2_2") (pintype "passive"))
      (node (ref "R3") (pin "2") (pinfunction "2_2") (pintype "passive"))
      (node (ref "SP2") (pin "1") (pinfunction "1_1") (pintype "passive"))
      (node (ref "TP5") (pin "1") (pinfunction "1_1") (pintype "passive"))
      (node (ref "U1") (pin "1") (pinfunction "GND_1") (pintype "passive"))
      (node (ref "U2") (pin "1") (pinfunction "GND_1") (pintype "passive"))
      (node (ref "U3") (pin "1") (pinfunction "GND_1") (pintype "passive"))
      (node (ref "U4") (pin "2") (pinfunction "GND_2") (pintype "passive"))
      (node (ref "U5") (pin "1") (pinfunction "GND_1") (pintype "passive"))
    )
    (net (code "17") (name "IO0") (class "Default")
      (node (ref "Q2") (pin "3") (pinfunction "C_3") (pintype "passive"))
    )
    (net (code "18") (name "Net-(C18-Pad1)") (class "Default")
      (node (ref "C18") (pin "1") (pinfunction "1_1") (pintype "passive"))
      (node (ref "D4") (pin "2") (pinfunction "2_2") (pintype "passive"))
      (node (ref "L2") (pin "1") (pinfunction "1_1") (pintype "passive"))
    )
    (net (code "19") (name "Net-(C18-Pad2)") (class "Default")
      (node (ref "C18") (pin "2") (pinfunction "2_2") (pintype "passive"))
      (node (ref "C19") (pin "1") (pinfunction "1_1") (pintype "passive"))
      (node (ref "D5") (pin "2") (pinfunction "2_2") (pintype "passive"))
      (node (ref "L4") (pin "2") (pinfunction "2_2") (pintype "passive"))
    )
    (net (code "20") (name "Net-(C19-Pad2)") (class "Default")
      (node (ref "C19") (pin "2") (pinfunction "2_2") (pintype "passive"))
      (node (ref "L5") (pin "2") (pinfunction "2_2") (pintype "passive"))
      (node (ref "U3") (pin "3") (pinfunction "SW_3") (pintype "passive"))
    )
    (net (code "21") (name "Net-(D3-Pad2)") (class "Default")
      (node (ref "D3") (pin "2") (pinfunction "2_2") (pintype "passive"))
      (node (ref "R6") (pin "1") (pinfunction "1_1") (pintype "passive"))
    )
    (net (code "22") (name "Net-(J1-CC1)") (class "Default")
      (node (ref "J1") (pin "4") (pinfunction "CC1_4") (pintype "passive"))
      (node (ref "R2") (pin "1") (pinfunction "1_1") (pintype "passive"))
    )
    (net (code "23") (name "Net-(J1-CC2)") (class "Default")
      (node (ref "J1") (pin "10") (pinfunction "CC2_10") (pintype "passive"))
      (node (ref "R1") (pin "1") (pinfunction "1_1") (pintype "passive"))
    )
    (net (code "24") (name "Net-(J1-DN1)") (class "Default")
      (node (ref "J1") (pin "5") (pinfunction "DN2_5") (pintype "passive"))
      (node (ref "J1") (pin "7") (pinfunction "DN1_7") (pintype "passive"))
      (node (ref "R5") (pin "1") (pinfunction "1_1") (pintype "passive"))
    )
    (net (code "25") (name "Net-(J1-DP1)") (class "Default")
      (node (ref "J1") (pin "6") (pinfunction "DP1_6") (pintype "passive"))
      (node (ref "J1") (pin "8") (pinfunction "DP2_8") (pintype "passive"))
      (node (ref "R4") (pin "1") (pinfunction "1_1") (pintype "passive"))
    )
    (net (code "26") (name "Net-(J2-D)") (class "Default")
      (node (ref "J2") (pin "3") (pinfunction "D_3") (pintype "passive"))
      (node (ref "U2") (pin "3") (pinfunction "VIN_3") (pintype "passive"))
    )
    (net (code "27") (name "Net-(J2-G)") (class "Default")
      (node (ref "J2") (pin "1") (pinfunction "G_1") (pintype "passive"))
      (node (ref "R3") (pin "1") (pinfunction "1_1") (pintype "passive"))
    )
    (net (code "28") (name "Net-(Q1-B)") (class "Default")
      (node (ref "Q1") (pin "1") (pinfunction "B_1") (pintype "passive"))
      (node (ref "R7") (pin "2") (pinfunction "2_2") (pintype "passive"))
    )
    (net (code "29") (name "Net-(Q2-B)") (class "Default")
      (node (ref "Q2") (pin "1") (pinfunction "B_1") (pintype "passive"))
      (node (ref "R8") (pin "2") (pinfunction "2_2") (pintype "passive"))
    )
    (net (code "30") (name "Net-(U3-FB)") (class "Default")
      (node (ref "R10") (pin "1") (pinfunction "1_1") (pintype "passive"))
      (node (ref "R12") (pin "2") (pinfunction "2_2") (pintype "passive"))
      (node (ref "TP8") (pin "1") (pinfunction "1_1") (pintype "passive"))
      (node (ref "U3") (pin "5") (pinfunction "FB_5") (pintype "passive"))
    )
    (net (code "31") (name "RST_CH340") (class "Default")
      (node (ref "Q1") (pin "2") (pinfunction "E_2") (pintype "passive"))
      (node (ref "R8") (pin "1") (pinfunction "1_1") (pintype "passive"))
      (node (ref "U1") (pin "14") (pinfunction "~{RTS}_14") (pintype "passive"))
    )
    (net (code "32") (name "RXD") (class "Default")
      (node (ref "U1") (pin "3") (pinfunction "RXD_3") (pintype "passive"))
    )
    (net (code "33") (name "TXD") (class "Default")
      (node (ref "U1") (pin "2") (pinfunction "TXD_2") (pintype "passive"))
    )
    (net (code "34") (name "V-BUS") (class "Default")
      (node (ref "C1") (pin "2") (pinfunction "2_2") (pintype "passive"))
      (node (ref "C24") (pin "2") (pinfunction "2_2") (pintype "passive"))
      (node (ref "C25") (pin "2") (pinfunction "2_2") (pintype "passive"))
      (node (ref "C26") (pin "2") (pinfunction "2_2") (pintype "passive"))
      (node (ref "C7") (pin "2") (pinfunction "2_2") (pintype "passive"))
      (node (ref "C8") (pin "2") (pinfunction "2_2") (pintype "passive"))
      (node (ref "C9") (pin "2") (pinfunction "2_2") (pintype "passive"))
      (node (ref "D2") (pin "2") (pinfunction "A_2") (pintype "passive"))
      (node (ref "J1") (pin "11") (pinfunction "VBUS_11") (pintype "passive"))
      (node (ref "J1") (pin "2") (pinfunction "VBUS_2") (pintype "passive"))
      (node (ref "J2") (pin "2") (pinfunction "S_2") (pintype "passive"))
      (node (ref "L5") (pin "1") (pinfunction "1_1") (pintype "passive"))
      (node (ref "R6") (pin "2") (pinfunction "2_2") (pintype "passive"))
      (node (ref "SP1") (pin "1") (pinfunction "1_1") (pintype "passive"))
      (node (ref "TP3") (pin "1") (pinfunction "1_1") (pintype "passive"))
      (node (ref "U3") (pin "2") (pinfunction "EN_2") (pintype "passive"))
      (node (ref "U3") (pin "4") (pinfunction "VIN_4") (pintype "passive"))
    )
    (net (code "35") (name "unconnected-(J1-SBU1-Pad9)") (class "Default")
      (node (ref "J1") (pin "9") (pinfunction "SBU1_9") (pintype "passive+no_connect"))
    )
    (net (code "36") (name "unconnected-(J1-SBU2-Pad3)") (class "Default")
      (node (ref "J1") (pin "3") (pinfunction "SBU2_3") (pintype "passive+no_connect"))
    )
    (net (code "37") (name "unconnected-(U1-NC-Pad7)") (class "Default")
      (node (ref "U1") (pin "7") (pinfunction "NC_7") (pintype "passive+no_connect"))
    )
    (net (code "38") (name "unconnected-(U1-R232-Pad15)") (class "Default")
      (node (ref "U1") (pin "15") (pinfunction "R232_15") (pintype "passive+no_connect"))
    )
    (net (code "39") (name "unconnected-(U1-~{CTS}-Pad9)") (class "Default")
      (node (ref "U1") (pin "9") (pinfunction "~{CTS}_9") (pintype "passive+no_connect"))
    )
    (net (code "40") (name "unconnected-(U1-~{DCD}-Pad12)") (class "Default")
      (node (ref "U1") (pin "12") (pinfunction "~{DCD}_12") (pintype "passive+no_connect"))
    )
    (net (code "41") (name "unconnected-(U1-~{DSR}-Pad10)") (class "Default")
      (node (ref "U1") (pin "10") (pinfunction "~{DSR}_10") (pintype "passive+no_connect"))
    )
    (net (code "42") (name "unconnected-(U1-~{OU}T-Pad8)") (class "Default")
      (node (ref "U1") (pin "8") (pinfunction "~{OU}T_8") (pintype "passive+no_connect"))
    )
    (net (code "43") (name "unconnected-(U1-~{RI}-Pad11)") (class "Default")
      (node (ref "U1") (pin "11") (pinfunction "~{RI}_11") (pintype "passive+no_connect"))
    )
    (net (code "44") (name "unconnected-(U3-SW-Pad6)") (class "Default")
      (node (ref "U3") (pin "6") (pinfunction "SW_6") (pintype "passive+no_connect"))
    )
  )
)
